# Ver_5_MD_Nch.net
KiCad netlist of a schematic drawn in EAGLE
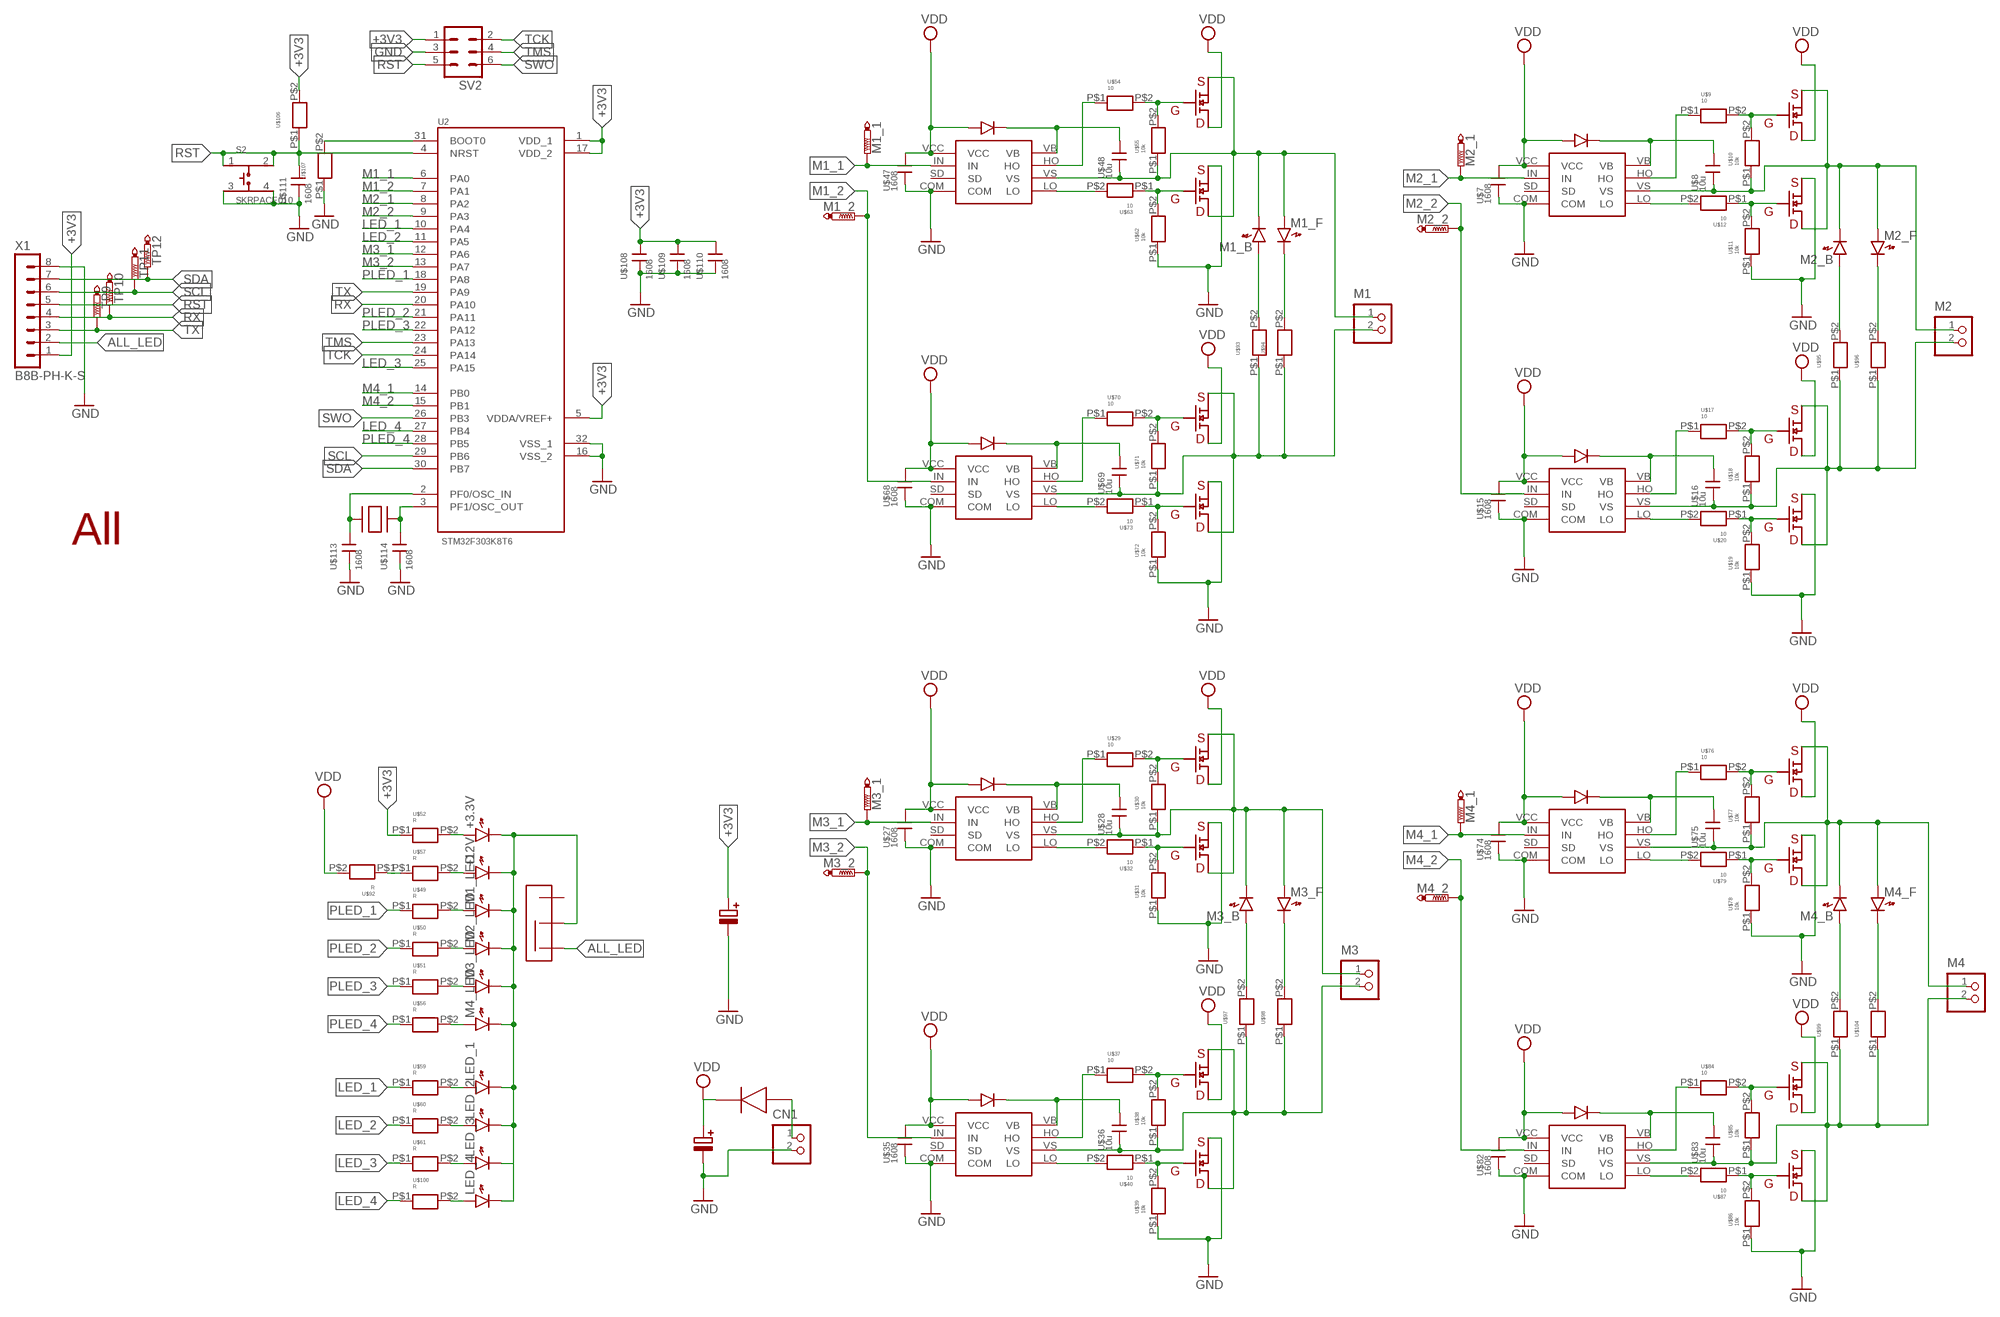
[diagram p0: schematic, sheet 1]

(export (version "E")
  (design (tool "Eeschema 10.0.6"))
  (components
    (comp (ref "+3.3V")
      (value "LED1608")
      (footprint "eagle-import:LED1608")
      (libsource (lib "eagle-import") (part "LED1608"))
    )
    (comp (ref "+12V")
      (value "LED1608")
      (footprint "eagle-import:LED1608")
      (libsource (lib "eagle-import") (part "LED1608"))
    )
    (comp (ref "CN1")
      (value "B2B-XH-A")
      (footprint "eagle-import:B2B-XH-A")
      (libsource (lib "eagle-import") (part "B2B-XH-A"))
    )
    (comp (ref "LED_1")
      (value "LED1608")
      (footprint "eagle-import:LED1608")
      (libsource (lib "eagle-import") (part "LED1608"))
    )
    (comp (ref "LED_2")
      (value "LED1608")
      (footprint "eagle-import:LED1608")
      (libsource (lib "eagle-import") (part "LED1608"))
    )
    (comp (ref "LED_3")
      (value "LED1608")
      (footprint "eagle-import:LED1608")
      (libsource (lib "eagle-import") (part "LED1608"))
    )
    (comp (ref "LED_4")
      (value "LED1608")
      (footprint "eagle-import:LED1608")
      (libsource (lib "eagle-import") (part "LED1608"))
    )
    (comp (ref "M1")
      (value "S2B-XH-A")
      (footprint "eagle-import:S2B-XH-A")
      (libsource (lib "eagle-import") (part "S2B-XH-A"))
    )
    (comp (ref "M1_1")
      (value "PTR1B1,27")
      (footprint "eagle-import:B1,27")
      (libsource (lib "eagle-import") (part "PTR1B1,27"))
    )
    (comp (ref "M1_2")
      (value "PTR1B1,27")
      (footprint "eagle-import:B1,27")
      (libsource (lib "eagle-import") (part "PTR1B1,27"))
    )
    (comp (ref "M1_B")
      (value "LED1608")
      (footprint "eagle-import:LED1608")
      (libsource (lib "eagle-import") (part "LED1608"))
    )
    (comp (ref "M1_F")
      (value "LED1608")
      (footprint "eagle-import:LED1608")
      (libsource (lib "eagle-import") (part "LED1608"))
    )
    (comp (ref "M1_LED")
      (value "LED1608")
      (footprint "eagle-import:LED1608")
      (libsource (lib "eagle-import") (part "LED1608"))
    )
    (comp (ref "M2")
      (value "S2B-XH-A")
      (footprint "eagle-import:S2B-XH-A")
      (libsource (lib "eagle-import") (part "S2B-XH-A"))
    )
    (comp (ref "M2_1")
      (value "PTR1B1,27")
      (footprint "eagle-import:B1,27")
      (libsource (lib "eagle-import") (part "PTR1B1,27"))
    )
    (comp (ref "M2_2")
      (value "PTR1B1,27")
      (footprint "eagle-import:B1,27")
      (libsource (lib "eagle-import") (part "PTR1B1,27"))
    )
    (comp (ref "M2_B")
      (value "LED1608")
      (footprint "eagle-import:LED1608")
      (libsource (lib "eagle-import") (part "LED1608"))
    )
    (comp (ref "M2_F")
      (value "LED1608")
      (footprint "eagle-import:LED1608")
      (libsource (lib "eagle-import") (part "LED1608"))
    )
    (comp (ref "M2_LED")
      (value "LED1608")
      (footprint "eagle-import:LED1608")
      (libsource (lib "eagle-import") (part "LED1608"))
    )
    (comp (ref "M3")
      (value "S2B-XH-A")
      (footprint "eagle-import:S2B-XH-A")
      (libsource (lib "eagle-import") (part "S2B-XH-A"))
    )
    (comp (ref "M3_1")
      (value "PTR1B1,27")
      (footprint "eagle-import:B1,27")
      (libsource (lib "eagle-import") (part "PTR1B1,27"))
    )
    (comp (ref "M3_2")
      (value "PTR1B1,27")
      (footprint "eagle-import:B1,27")
      (libsource (lib "eagle-import") (part "PTR1B1,27"))
    )
    (comp (ref "M3_B")
      (value "LED1608")
      (footprint "eagle-import:LED1608")
      (libsource (lib "eagle-import") (part "LED1608"))
    )
    (comp (ref "M3_F")
      (value "LED1608")
      (footprint "eagle-import:LED1608")
      (libsource (lib "eagle-import") (part "LED1608"))
    )
    (comp (ref "M3_LED")
      (value "LED1608")
      (footprint "eagle-import:LED1608")
      (libsource (lib "eagle-import") (part "LED1608"))
    )
    (comp (ref "M4")
      (value "S2B-XH-A")
      (footprint "eagle-import:S2B-XH-A")
      (libsource (lib "eagle-import") (part "S2B-XH-A"))
    )
    (comp (ref "M4_1")
      (value "PTR1B1,27")
      (footprint "eagle-import:B1,27")
      (libsource (lib "eagle-import") (part "PTR1B1,27"))
    )
    (comp (ref "M4_2")
      (value "PTR1B1,27")
      (footprint "eagle-import:B1,27")
      (libsource (lib "eagle-import") (part "PTR1B1,27"))
    )
    (comp (ref "M4_B")
      (value "LED1608")
      (footprint "eagle-import:LED1608")
      (libsource (lib "eagle-import") (part "LED1608"))
    )
    (comp (ref "M4_F")
      (value "LED1608")
      (footprint "eagle-import:LED1608")
      (libsource (lib "eagle-import") (part "LED1608"))
    )
    (comp (ref "M4_LED")
      (value "LED1608")
      (footprint "eagle-import:LED1608")
      (libsource (lib "eagle-import") (part "LED1608"))
    )
    (comp (ref "S2")
      (value "SKRPACE010")
      (footprint "eagle-import:SW_SKRPACE010")
      (fields (field (name "MF") "ALPS"))
      (libsource (lib "eagle-import") (part "SKRPACE010"))
    )
    (comp (ref "SV2")
      (value "ML6")
      (footprint "eagle-import:ML6")
      (libsource (lib "eagle-import") (part "ML6"))
    )
    (comp (ref "TP9")
      (value "PTR1B1,27")
      (footprint "eagle-import:B1,27")
      (libsource (lib "eagle-import") (part "PTR1B1,27"))
    )
    (comp (ref "TP10")
      (value "PTR1B1,27")
      (footprint "eagle-import:B1,27")
      (libsource (lib "eagle-import") (part "PTR1B1,27"))
    )
    (comp (ref "TP11")
      (value "PTR1B1,27")
      (footprint "eagle-import:B1,27")
      (libsource (lib "eagle-import") (part "PTR1B1,27"))
    )
    (comp (ref "TP12")
      (value "PTR1B1,27")
      (footprint "eagle-import:B1,27")
      (libsource (lib "eagle-import") (part "PTR1B1,27"))
    )
    (comp (ref "U$1")
      (value "SSM6K8")
      (footprint "eagle-import:SSM6K8")
      (libsource (lib "eagle-import") (part "SSM6K8"))
    )
    (comp (ref "U$2")
      (value "SSM6K8")
      (footprint "eagle-import:SSM6K8")
      (libsource (lib "eagle-import") (part "SSM6K8"))
    )
    (comp (ref "U$3")
      (value "SSM6K8")
      (footprint "eagle-import:SSM6K8")
      (libsource (lib "eagle-import") (part "SSM6K8"))
    )
    (comp (ref "U$4")
      (value "SSM6K8")
      (footprint "eagle-import:SSM6K8")
      (libsource (lib "eagle-import") (part "SSM6K8"))
    )
    (comp (ref "U$5")
      (value "IR2302")
      (footprint "eagle-import:IR2302")
      (libsource (lib "eagle-import") (part "IR2302"))
    )
    (comp (ref "U$6")
      (value "1N4148")
      (footprint "eagle-import:1N4148")
      (libsource (lib "eagle-import") (part "1N4148"))
    )
    (comp (ref "U$7")
      (value "1608")
      (footprint "eagle-import:CON")
      (libsource (lib "eagle-import") (part "1608"))
    )
    (comp (ref "U$8")
      (value "10u")
      (footprint "eagle-import:CON")
      (libsource (lib "eagle-import") (part "1608"))
    )
    (comp (ref "U$9")
      (value "10")
      (footprint "eagle-import:1608")
      (libsource (lib "eagle-import") (part "R"))
    )
    (comp (ref "U$10")
      (value "10k")
      (footprint "eagle-import:1608")
      (libsource (lib "eagle-import") (part "R"))
    )
    (comp (ref "U$11")
      (value "10k")
      (footprint "eagle-import:1608")
      (libsource (lib "eagle-import") (part "R"))
    )
    (comp (ref "U$12")
      (value "10")
      (footprint "eagle-import:1608")
      (libsource (lib "eagle-import") (part "R"))
    )
    (comp (ref "U$13")
      (value "IR2302")
      (footprint "eagle-import:IR2302")
      (libsource (lib "eagle-import") (part "IR2302"))
    )
    (comp (ref "U$14")
      (value "1N4148")
      (footprint "eagle-import:1N4148")
      (libsource (lib "eagle-import") (part "1N4148"))
    )
    (comp (ref "U$15")
      (value "1608")
      (footprint "eagle-import:CON")
      (libsource (lib "eagle-import") (part "1608"))
    )
    (comp (ref "U$16")
      (value "10u")
      (footprint "eagle-import:CON")
      (libsource (lib "eagle-import") (part "1608"))
    )
    (comp (ref "U$17")
      (value "10")
      (footprint "eagle-import:1608")
      (libsource (lib "eagle-import") (part "R"))
    )
    (comp (ref "U$18")
      (value "10k")
      (footprint "eagle-import:1608")
      (libsource (lib "eagle-import") (part "R"))
    )
    (comp (ref "U$19")
      (value "10k")
      (footprint "eagle-import:1608")
      (libsource (lib "eagle-import") (part "R"))
    )
    (comp (ref "U$20")
      (value "10")
      (footprint "eagle-import:1608")
      (libsource (lib "eagle-import") (part "R"))
    )
    (comp (ref "U$21")
      (value "SSM6K8")
      (footprint "eagle-import:SSM6K8")
      (libsource (lib "eagle-import") (part "SSM6K8"))
    )
    (comp (ref "U$22")
      (value "SSM6K8")
      (footprint "eagle-import:SSM6K8")
      (libsource (lib "eagle-import") (part "SSM6K8"))
    )
    (comp (ref "U$23")
      (value "SSM6K8")
      (footprint "eagle-import:SSM6K8")
      (libsource (lib "eagle-import") (part "SSM6K8"))
    )
    (comp (ref "U$24")
      (value "SSM6K8")
      (footprint "eagle-import:SSM6K8")
      (libsource (lib "eagle-import") (part "SSM6K8"))
    )
    (comp (ref "U$25")
      (value "IR2302")
      (footprint "eagle-import:IR2302")
      (libsource (lib "eagle-import") (part "IR2302"))
    )
    (comp (ref "U$26")
      (value "1N4148")
      (footprint "eagle-import:1N4148")
      (libsource (lib "eagle-import") (part "1N4148"))
    )
    (comp (ref "U$27")
      (value "1608")
      (footprint "eagle-import:CON")
      (libsource (lib "eagle-import") (part "1608"))
    )
    (comp (ref "U$28")
      (value "10u")
      (footprint "eagle-import:CON")
      (libsource (lib "eagle-import") (part "1608"))
    )
    (comp (ref "U$29")
      (value "10")
      (footprint "eagle-import:1608")
      (libsource (lib "eagle-import") (part "R"))
    )
    (comp (ref "U$30")
      (value "10k")
      (footprint "eagle-import:1608")
      (libsource (lib "eagle-import") (part "R"))
    )
    (comp (ref "U$31")
      (value "10k")
      (footprint "eagle-import:1608")
      (libsource (lib "eagle-import") (part "R"))
    )
    (comp (ref "U$32")
      (value "10")
      (footprint "eagle-import:1608")
      (libsource (lib "eagle-import") (part "R"))
    )
    (comp (ref "U$33")
      (value "IR2302")
      (footprint "eagle-import:IR2302")
      (libsource (lib "eagle-import") (part "IR2302"))
    )
    (comp (ref "U$34")
      (value "1N4148")
      (footprint "eagle-import:1N4148")
      (libsource (lib "eagle-import") (part "1N4148"))
    )
    (comp (ref "U$35")
      (value "1608")
      (footprint "eagle-import:CON")
      (libsource (lib "eagle-import") (part "1608"))
    )
    (comp (ref "U$36")
      (value "10u")
      (footprint "eagle-import:CON")
      (libsource (lib "eagle-import") (part "1608"))
    )
    (comp (ref "U$37")
      (value "10")
      (footprint "eagle-import:1608")
      (libsource (lib "eagle-import") (part "R"))
    )
    (comp (ref "U$38")
      (value "10k")
      (footprint "eagle-import:1608")
      (libsource (lib "eagle-import") (part "R"))
    )
    (comp (ref "U$39")
      (value "10k")
      (footprint "eagle-import:1608")
      (libsource (lib "eagle-import") (part "R"))
    )
    (comp (ref "U$40")
      (value "10")
      (footprint "eagle-import:1608")
      (libsource (lib "eagle-import") (part "R"))
    )
    (comp (ref "U$41")
      (value "SSM6K8")
      (footprint "eagle-import:SSM6K8")
      (libsource (lib "eagle-import") (part "SSM6K8"))
    )
    (comp (ref "U$42")
      (value "SSM6K8")
      (footprint "eagle-import:SSM6K8")
      (libsource (lib "eagle-import") (part "SSM6K8"))
    )
    (comp (ref "U$43")
      (value "SSM6K8")
      (footprint "eagle-import:SSM6K8")
      (libsource (lib "eagle-import") (part "SSM6K8"))
    )
    (comp (ref "U$44")
      (value "SSM6K8")
      (footprint "eagle-import:SSM6K8")
      (libsource (lib "eagle-import") (part "SSM6K8"))
    )
    (comp (ref "U$45")
      (value "IR2302")
      (footprint "eagle-import:IR2302")
      (libsource (lib "eagle-import") (part "IR2302"))
    )
    (comp (ref "U$46")
      (value "1N4148")
      (footprint "eagle-import:1N4148")
      (libsource (lib "eagle-import") (part "1N4148"))
    )
    (comp (ref "U$47")
      (value "1608")
      (footprint "eagle-import:CON")
      (libsource (lib "eagle-import") (part "1608"))
    )
    (comp (ref "U$48")
      (value "10u")
      (footprint "eagle-import:CON")
      (libsource (lib "eagle-import") (part "1608"))
    )
    (comp (ref "U$49")
      (value "R")
      (footprint "eagle-import:1608")
      (libsource (lib "eagle-import") (part "R"))
    )
    (comp (ref "U$50")
      (value "R")
      (footprint "eagle-import:1608")
      (libsource (lib "eagle-import") (part "R"))
    )
    (comp (ref "U$51")
      (value "R")
      (footprint "eagle-import:1608")
      (libsource (lib "eagle-import") (part "R"))
    )
    (comp (ref "U$52")
      (value "R")
      (footprint "eagle-import:1608")
      (libsource (lib "eagle-import") (part "R"))
    )
    (comp (ref "U$53")
      (value "SSW")
      (footprint "eagle-import:SSW")
      (libsource (lib "eagle-import") (part "SSW"))
    )
    (comp (ref "U$54")
      (value "10")
      (footprint "eagle-import:1608")
      (libsource (lib "eagle-import") (part "R"))
    )
    (comp (ref "U$55")
      (value "10k")
      (footprint "eagle-import:1608")
      (libsource (lib "eagle-import") (part "R"))
    )
    (comp (ref "U$56")
      (value "R")
      (footprint "eagle-import:1608")
      (libsource (lib "eagle-import") (part "R"))
    )
    (comp (ref "U$57")
      (value "R")
      (footprint "eagle-import:1608")
      (libsource (lib "eagle-import") (part "R"))
    )
    (comp (ref "U$58")
      (value "25V100")
      (footprint "eagle-import:25V100")
      (libsource (lib "eagle-import") (part "25V100"))
    )
    (comp (ref "U$59")
      (value "R")
      (footprint "eagle-import:1608")
      (libsource (lib "eagle-import") (part "R"))
    )
    (comp (ref "U$60")
      (value "R")
      (footprint "eagle-import:1608")
      (libsource (lib "eagle-import") (part "R"))
    )
    (comp (ref "U$61")
      (value "R")
      (footprint "eagle-import:1608")
      (libsource (lib "eagle-import") (part "R"))
    )
    (comp (ref "U$62")
      (value "10k")
      (footprint "eagle-import:1608")
      (libsource (lib "eagle-import") (part "R"))
    )
    (comp (ref "U$63")
      (value "10")
      (footprint "eagle-import:1608")
      (libsource (lib "eagle-import") (part "R"))
    )
    (comp (ref "U$64")
      (value "IR2302")
      (footprint "eagle-import:IR2302")
      (libsource (lib "eagle-import") (part "IR2302"))
    )
    (comp (ref "U$65")
      (value "1N4148")
      (footprint "eagle-import:1N4148")
      (libsource (lib "eagle-import") (part "1N4148"))
    )
    (comp (ref "U$66")
      (value "IR2302")
      (footprint "eagle-import:IR2302")
      (libsource (lib "eagle-import") (part "IR2302"))
    )
    (comp (ref "U$67")
      (value "1N4148")
      (footprint "eagle-import:1N4148")
      (libsource (lib "eagle-import") (part "1N4148"))
    )
    (comp (ref "U$68")
      (value "1608")
      (footprint "eagle-import:CON")
      (libsource (lib "eagle-import") (part "1608"))
    )
    (comp (ref "U$69")
      (value "10u")
      (footprint "eagle-import:CON")
      (libsource (lib "eagle-import") (part "1608"))
    )
    (comp (ref "U$70")
      (value "10")
      (footprint "eagle-import:1608")
      (libsource (lib "eagle-import") (part "R"))
    )
    (comp (ref "U$71")
      (value "10k")
      (footprint "eagle-import:1608")
      (libsource (lib "eagle-import") (part "R"))
    )
    (comp (ref "U$72")
      (value "10k")
      (footprint "eagle-import:1608")
      (libsource (lib "eagle-import") (part "R"))
    )
    (comp (ref "U$73")
      (value "10")
      (footprint "eagle-import:1608")
      (libsource (lib "eagle-import") (part "R"))
    )
    (comp (ref "U$74")
      (value "1608")
      (footprint "eagle-import:CON")
      (libsource (lib "eagle-import") (part "1608"))
    )
    (comp (ref "U$75")
      (value "10u")
      (footprint "eagle-import:CON")
      (libsource (lib "eagle-import") (part "1608"))
    )
    (comp (ref "U$76")
      (value "10")
      (footprint "eagle-import:1608")
      (libsource (lib "eagle-import") (part "R"))
    )
    (comp (ref "U$77")
      (value "10k")
      (footprint "eagle-import:1608")
      (libsource (lib "eagle-import") (part "R"))
    )
    (comp (ref "U$78")
      (value "10k")
      (footprint "eagle-import:1608")
      (libsource (lib "eagle-import") (part "R"))
    )
    (comp (ref "U$79")
      (value "10")
      (footprint "eagle-import:1608")
      (libsource (lib "eagle-import") (part "R"))
    )
    (comp (ref "U$80")
      (value "IR2302")
      (footprint "eagle-import:IR2302")
      (libsource (lib "eagle-import") (part "IR2302"))
    )
    (comp (ref "U$81")
      (value "1N4148")
      (footprint "eagle-import:1N4148")
      (libsource (lib "eagle-import") (part "1N4148"))
    )
    (comp (ref "U$82")
      (value "1608")
      (footprint "eagle-import:CON")
      (libsource (lib "eagle-import") (part "1608"))
    )
    (comp (ref "U$83")
      (value "10u")
      (footprint "eagle-import:CON")
      (libsource (lib "eagle-import") (part "1608"))
    )
    (comp (ref "U$84")
      (value "10")
      (footprint "eagle-import:1608")
      (libsource (lib "eagle-import") (part "R"))
    )
    (comp (ref "U$85")
      (value "10k")
      (footprint "eagle-import:1608")
      (libsource (lib "eagle-import") (part "R"))
    )
    (comp (ref "U$86")
      (value "10k")
      (footprint "eagle-import:1608")
      (libsource (lib "eagle-import") (part "R"))
    )
    (comp (ref "U$87")
      (value "10")
      (footprint "eagle-import:1608")
      (libsource (lib "eagle-import") (part "R"))
    )
    (comp (ref "U$88")
      (value "SSM6K8")
      (footprint "eagle-import:SSM6K8")
      (libsource (lib "eagle-import") (part "SSM6K8"))
    )
    (comp (ref "U$89")
      (value "SSM6K8")
      (footprint "eagle-import:SSM6K8")
      (libsource (lib "eagle-import") (part "SSM6K8"))
    )
    (comp (ref "U$90")
      (value "SSM6K8")
      (footprint "eagle-import:SSM6K8")
      (libsource (lib "eagle-import") (part "SSM6K8"))
    )
    (comp (ref "U$91")
      (value "SSM6K8")
      (footprint "eagle-import:SSM6K8")
      (libsource (lib "eagle-import") (part "SSM6K8"))
    )
    (comp (ref "U$92")
      (value "R")
      (footprint "eagle-import:1608")
      (libsource (lib "eagle-import") (part "R"))
    )
    (comp (ref "U$93")
      (value "R")
      (footprint "eagle-import:1608")
      (libsource (lib "eagle-import") (part "R"))
    )
    (comp (ref "U$94")
      (value "R")
      (footprint "eagle-import:1608")
      (libsource (lib "eagle-import") (part "R"))
    )
    (comp (ref "U$95")
      (value "R")
      (footprint "eagle-import:1608")
      (libsource (lib "eagle-import") (part "R"))
    )
    (comp (ref "U$96")
      (value "R")
      (footprint "eagle-import:1608")
      (libsource (lib "eagle-import") (part "R"))
    )
    (comp (ref "U$97")
      (value "R")
      (footprint "eagle-import:1608")
      (libsource (lib "eagle-import") (part "R"))
    )
    (comp (ref "U$98")
      (value "R")
      (footprint "eagle-import:1608")
      (libsource (lib "eagle-import") (part "R"))
    )
    (comp (ref "U$99")
      (value "R")
      (footprint "eagle-import:1608")
      (libsource (lib "eagle-import") (part "R"))
    )
    (comp (ref "U$100")
      (value "R")
      (footprint "eagle-import:1608")
      (libsource (lib "eagle-import") (part "R"))
    )
    (comp (ref "U$101")
      (value "25V100")
      (footprint "eagle-import:25V100")
      (libsource (lib "eagle-import") (part "25V100"))
    )
    (comp (ref "U$102")
      (value "40V5A")
      (footprint "eagle-import:40V5A")
      (libsource (lib "eagle-import") (part "40V5A"))
    )
    (comp (ref "U$103")
      (value "ALL")
      (footprint "eagle-import:ALL")
      (libsource (lib "eagle-import") (part "ALL"))
    )
    (comp (ref "U$104")
      (value "R")
      (footprint "eagle-import:1608")
      (libsource (lib "eagle-import") (part "R"))
    )
    (comp (ref "U$106")
      (value "R")
      (footprint "eagle-import:1608")
      (libsource (lib "eagle-import") (part "R"))
    )
    (comp (ref "U$107")
      (value "R")
      (footprint "eagle-import:1608")
      (libsource (lib "eagle-import") (part "R"))
    )
    (comp (ref "U$108")
      (value "1608")
      (footprint "eagle-import:CON")
      (libsource (lib "eagle-import") (part "1608"))
    )
    (comp (ref "U$109")
      (value "1608")
      (footprint "eagle-import:CON")
      (libsource (lib "eagle-import") (part "1608"))
    )
    (comp (ref "U$110")
      (value "1608")
      (footprint "eagle-import:CON")
      (libsource (lib "eagle-import") (part "1608"))
    )
    (comp (ref "U$111")
      (value "1608")
      (footprint "eagle-import:CON")
      (libsource (lib "eagle-import") (part "1608"))
    )
    (comp (ref "U$112")
      (value "SUISYOU")
      (footprint "eagle-import:水晶")
      (libsource (lib "eagle-import") (part "SUISYOU"))
    )
    (comp (ref "U$113")
      (value "1608")
      (footprint "eagle-import:CON")
      (libsource (lib "eagle-import") (part "1608"))
    )
    (comp (ref "U$114")
      (value "1608")
      (footprint "eagle-import:CON")
      (libsource (lib "eagle-import") (part "1608"))
    )
    (comp (ref "U2")
      (value "STM32F303K8T6")
      (footprint "eagle-import:QFP80P900X900X160-32N")
      (fields (field (name "MF") "STMicroelectronics"))
      (libsource (lib "eagle-import") (part "STM32F303K8T6"))
    )
    (comp (ref "X1")
      (value "B8B-PH-K-S")
      (footprint "eagle-import:B8B-PH-K-S")
      (libsource (lib "eagle-import") (part "B8B-PH-K-S"))
    )
  )
  (nets
    (net (code "1") (name "+3V3") (class "Default")
      (node (ref "SV2") (pin "1") (pinfunction "1_1") (pintype "passive"))
      (node (ref "U$106") (pin "P$2") (pinfunction "P$2_P$2") (pintype "bidirectional"))
      (node (ref "U$108") (pin "P$1") (pinfunction "1_P$1") (pintype "bidirectional"))
      (node (ref "U$109") (pin "P$1") (pinfunction "1_P$1") (pintype "bidirectional"))
      (node (ref "U$110") (pin "P$1") (pinfunction "1_P$1") (pintype "bidirectional"))
      (node (ref "U$52") (pin "P$1") (pinfunction "P$1_P$1") (pintype "bidirectional"))
      (node (ref "U$58") (pin "P$1") (pinfunction "P$1_P$1") (pintype "bidirectional"))
      (node (ref "U2") (pin "1") (pinfunction "VDD_1_1") (pintype "power_in"))
      (node (ref "U2") (pin "17") (pinfunction "VDD_2_17") (pintype "power_in"))
      (node (ref "U2") (pin "5") (pinfunction "VDDA/VREF+_5") (pintype "power_in"))
      (node (ref "X1") (pin "1") (pinfunction "1_1") (pintype "passive"))
    )
    (net (code "2") (name "ALL_LED") (class "Default")
      (node (ref "U$53") (pin "P$1") (pinfunction "P$1_P$1") (pintype "bidirectional"))
      (node (ref "X1") (pin "2") (pinfunction "2_2") (pintype "passive"))
    )
    (net (code "3") (name "GND") (class "Default")
      (node (ref "CN1") (pin "2") (pinfunction "2_2") (pintype "passive"))
      (node (ref "S2") (pin "3") (pinfunction "3_3") (pintype "bidirectional"))
      (node (ref "S2") (pin "4") (pinfunction "4_4") (pintype "bidirectional"))
      (node (ref "SV2") (pin "3") (pinfunction "3_3") (pintype "passive"))
      (node (ref "U$101") (pin "P$2") (pinfunction "P$2_P$2") (pintype "bidirectional"))
      (node (ref "U$107") (pin "P$1") (pinfunction "P$1_P$1") (pintype "bidirectional"))
      (node (ref "U$108") (pin "P$2") (pinfunction "2_P$2") (pintype "bidirectional"))
      (node (ref "U$109") (pin "P$2") (pinfunction "2_P$2") (pintype "bidirectional"))
      (node (ref "U$11") (pin "P$1") (pinfunction "P$1_P$1") (pintype "bidirectional"))
      (node (ref "U$110") (pin "P$2") (pinfunction "2_P$2") (pintype "bidirectional"))
      (node (ref "U$111") (pin "P$2") (pinfunction "2_P$2") (pintype "bidirectional"))
      (node (ref "U$113") (pin "P$2") (pinfunction "2_P$2") (pintype "bidirectional"))
      (node (ref "U$114") (pin "P$2") (pinfunction "2_P$2") (pintype "bidirectional"))
      (node (ref "U$13") (pin "COM") (pinfunction "COM_COM") (pintype "bidirectional"))
      (node (ref "U$15") (pin "P$2") (pinfunction "2_P$2") (pintype "bidirectional"))
      (node (ref "U$19") (pin "P$1") (pinfunction "P$1_P$1") (pintype "bidirectional"))
      (node (ref "U$2") (pin "S") (pinfunction "S_S") (pintype "bidirectional"))
      (node (ref "U$22") (pin "S") (pinfunction "S_S") (pintype "bidirectional"))
      (node (ref "U$24") (pin "S") (pinfunction "S_S") (pintype "bidirectional"))
      (node (ref "U$25") (pin "COM") (pinfunction "COM_COM") (pintype "bidirectional"))
      (node (ref "U$27") (pin "P$2") (pinfunction "2_P$2") (pintype "bidirectional"))
      (node (ref "U$31") (pin "P$1") (pinfunction "P$1_P$1") (pintype "bidirectional"))
      (node (ref "U$33") (pin "COM") (pinfunction "COM_COM") (pintype "bidirectional"))
      (node (ref "U$35") (pin "P$2") (pinfunction "2_P$2") (pintype "bidirectional"))
      (node (ref "U$39") (pin "P$1") (pinfunction "P$1_P$1") (pintype "bidirectional"))
      (node (ref "U$4") (pin "S") (pinfunction "S_S") (pintype "bidirectional"))
      (node (ref "U$42") (pin "S") (pinfunction "S_S") (pintype "bidirectional"))
      (node (ref "U$44") (pin "S") (pinfunction "S_S") (pintype "bidirectional"))
      (node (ref "U$45") (pin "COM") (pinfunction "COM_COM") (pintype "bidirectional"))
      (node (ref "U$47") (pin "P$2") (pinfunction "2_P$2") (pintype "bidirectional"))
      (node (ref "U$5") (pin "COM") (pinfunction "COM_COM") (pintype "bidirectional"))
      (node (ref "U$58") (pin "P$2") (pinfunction "P$2_P$2") (pintype "bidirectional"))
      (node (ref "U$62") (pin "P$1") (pinfunction "P$1_P$1") (pintype "bidirectional"))
      (node (ref "U$64") (pin "COM") (pinfunction "COM_COM") (pintype "bidirectional"))
      (node (ref "U$66") (pin "COM") (pinfunction "COM_COM") (pintype "bidirectional"))
      (node (ref "U$68") (pin "P$2") (pinfunction "2_P$2") (pintype "bidirectional"))
      (node (ref "U$7") (pin "P$2") (pinfunction "2_P$2") (pintype "bidirectional"))
      (node (ref "U$72") (pin "P$1") (pinfunction "P$1_P$1") (pintype "bidirectional"))
      (node (ref "U$74") (pin "P$2") (pinfunction "2_P$2") (pintype "bidirectional"))
      (node (ref "U$78") (pin "P$1") (pinfunction "P$1_P$1") (pintype "bidirectional"))
      (node (ref "U$80") (pin "COM") (pinfunction "COM_COM") (pintype "bidirectional"))
      (node (ref "U$82") (pin "P$2") (pinfunction "2_P$2") (pintype "bidirectional"))
      (node (ref "U$86") (pin "P$1") (pinfunction "P$1_P$1") (pintype "bidirectional"))
      (node (ref "U$89") (pin "S") (pinfunction "S_S") (pintype "bidirectional"))
      (node (ref "U$91") (pin "S") (pinfunction "S_S") (pintype "bidirectional"))
      (node (ref "U2") (pin "16") (pinfunction "VSS_2_16") (pintype "power_in"))
      (node (ref "U2") (pin "32") (pinfunction "VSS_1_32") (pintype "power_in"))
      (node (ref "X1") (pin "8") (pinfunction "8_8") (pintype "passive"))
    )
    (net (code "4") (name "LED_1") (class "Default")
      (node (ref "U$59") (pin "P$1") (pinfunction "P$1_P$1") (pintype "bidirectional"))
      (node (ref "U2") (pin "10") (pinfunction "PA4_10") (pintype "bidirectional"))
    )
    (net (code "5") (name "LED_2") (class "Default")
      (node (ref "U$60") (pin "P$1") (pinfunction "P$1_P$1") (pintype "bidirectional"))
      (node (ref "U2") (pin "11") (pinfunction "PA5_11") (pintype "bidirectional"))
    )
    (net (code "6") (name "LED_3") (class "Default")
      (node (ref "U$61") (pin "P$1") (pinfunction "P$1_P$1") (pintype "bidirectional"))
      (node (ref "U2") (pin "25") (pinfunction "PA15_25") (pintype "bidirectional"))
    )
    (net (code "7") (name "LED_4") (class "Default")
      (node (ref "U$100") (pin "P$1") (pinfunction "P$1_P$1") (pintype "bidirectional"))
      (node (ref "U2") (pin "27") (pinfunction "PB4_27") (pintype "bidirectional"))
    )
    (net (code "8") (name "M1_1") (class "Default")
      (node (ref "M1_1") (pin "TP") (pinfunction "TP_TP") (pintype "input"))
      (node (ref "U$45") (pin "IN") (pinfunction "IN_IN") (pintype "bidirectional"))
      (node (ref "U2") (pin "6") (pinfunction "PA0_6") (pintype "bidirectional"))
    )
    (net (code "9") (name "M1_2") (class "Default")
      (node (ref "M1_2") (pin "TP") (pinfunction "TP_TP") (pintype "input"))
      (node (ref "U$66") (pin "IN") (pinfunction "IN_IN") (pintype "bidirectional"))
      (node (ref "U2") (pin "7") (pinfunction "PA1_7") (pintype "bidirectional"))
    )
    (net (code "10") (name "M2_1") (class "Default")
      (node (ref "M2_1") (pin "TP") (pinfunction "TP_TP") (pintype "input"))
      (node (ref "U$5") (pin "IN") (pinfunction "IN_IN") (pintype "bidirectional"))
      (node (ref "U2") (pin "8") (pinfunction "PA2_8") (pintype "bidirectional"))
    )
    (net (code "11") (name "M2_2") (class "Default")
      (node (ref "M2_2") (pin "TP") (pinfunction "TP_TP") (pintype "input"))
      (node (ref "U$13") (pin "IN") (pinfunction "IN_IN") (pintype "bidirectional"))
      (node (ref "U2") (pin "9") (pinfunction "PA3_9") (pintype "bidirectional"))
    )
    (net (code "12") (name "M3_1") (class "Default")
      (node (ref "M3_1") (pin "TP") (pinfunction "TP_TP") (pintype "input"))
      (node (ref "U$25") (pin "IN") (pinfunction "IN_IN") (pintype "bidirectional"))
      (node (ref "U2") (pin "12") (pinfunction "PA6_12") (pintype "bidirectional"))
    )
    (net (code "13") (name "M3_2") (class "Default")
      (node (ref "M3_2") (pin "TP") (pinfunction "TP_TP") (pintype "input"))
      (node (ref "U$33") (pin "IN") (pinfunction "IN_IN") (pintype "bidirectional"))
      (node (ref "U2") (pin "13") (pinfunction "PA7_13") (pintype "bidirectional"))
    )
    (net (code "14") (name "M4_1") (class "Default")
      (node (ref "M4_1") (pin "TP") (pinfunction "TP_TP") (pintype "input"))
      (node (ref "U$64") (pin "IN") (pinfunction "IN_IN") (pintype "bidirectional"))
      (node (ref "U2") (pin "14") (pinfunction "PB0_14") (pintype "bidirectional"))
    )
    (net (code "15") (name "M4_2") (class "Default")
      (node (ref "M4_2") (pin "TP") (pinfunction "TP_TP") (pintype "input"))
      (node (ref "U$80") (pin "IN") (pinfunction "IN_IN") (pintype "bidirectional"))
      (node (ref "U2") (pin "15") (pinfunction "PB1_15") (pintype "bidirectional"))
    )
    (net (code "16") (name "Net-(+3.3V-PadA)") (class "Default")
      (node (ref "+3.3V") (pin "A") (pinfunction "A_A") (pintype "passive"))
      (node (ref "U$52") (pin "P$2") (pinfunction "P$2_P$2") (pintype "bidirectional"))
    )
    (net (code "17") (name "Net-(+12V-PadA)") (class "Default")
      (node (ref "+12V") (pin "A") (pinfunction "A_A") (pintype "passive"))
      (node (ref "U$57") (pin "P$2") (pinfunction "P$2_P$2") (pintype "bidirectional"))
    )
    (net (code "18") (name "Net-(CN1-Pad1)") (class "Default")
      (node (ref "CN1") (pin "1") (pinfunction "1_1") (pintype "passive"))
      (node (ref "U$102") (pin "P$1") (pinfunction "P$1_P$1") (pintype "bidirectional"))
    )
    (net (code "19") (name "Net-(LED_1-PadA)") (class "Default")
      (node (ref "LED_1") (pin "A") (pinfunction "A_A") (pintype "passive"))
      (node (ref "U$59") (pin "P$2") (pinfunction "P$2_P$2") (pintype "bidirectional"))
    )
    (net (code "20") (name "Net-(LED_2-PadA)") (class "Default")
      (node (ref "LED_2") (pin "A") (pinfunction "A_A") (pintype "passive"))
      (node (ref "U$60") (pin "P$2") (pinfunction "P$2_P$2") (pintype "bidirectional"))
    )
    (net (code "21") (name "Net-(LED_3-PadA)") (class "Default")
      (node (ref "LED_3") (pin "A") (pinfunction "A_A") (pintype "passive"))
      (node (ref "U$61") (pin "P$2") (pinfunction "P$2_P$2") (pintype "bidirectional"))
    )
    (net (code "22") (name "Net-(LED_4-PadA)") (class "Default")
      (node (ref "LED_4") (pin "A") (pinfunction "A_A") (pintype "passive"))
      (node (ref "U$100") (pin "P$2") (pinfunction "P$2_P$2") (pintype "bidirectional"))
    )
    (net (code "23") (name "Net-(M1_B-PadA)") (class "Default")
      (node (ref "M1_B") (pin "A") (pinfunction "A_A") (pintype "passive"))
      (node (ref "U$93") (pin "P$2") (pinfunction "P$2_P$2") (pintype "bidirectional"))
    )
    (net (code "24") (name "Net-(M1_F-PadK)") (class "Default")
      (node (ref "M1_F") (pin "K") (pinfunction "K_K") (pintype "passive"))
      (node (ref "U$94") (pin "P$2") (pinfunction "P$2_P$2") (pintype "bidirectional"))
    )
    (net (code "25") (name "Net-(M1_LED-PadA)") (class "Default")
      (node (ref "M1_LED") (pin "A") (pinfunction "A_A") (pintype "passive"))
      (node (ref "U$49") (pin "P$2") (pinfunction "P$2_P$2") (pintype "bidirectional"))
    )
    (net (code "26") (name "Net-(M2_B-PadA)") (class "Default")
      (node (ref "M2_B") (pin "A") (pinfunction "A_A") (pintype "passive"))
      (node (ref "U$95") (pin "P$2") (pinfunction "P$2_P$2") (pintype "bidirectional"))
    )
    (net (code "27") (name "Net-(M2_F-PadK)") (class "Default")
      (node (ref "M2_F") (pin "K") (pinfunction "K_K") (pintype "passive"))
      (node (ref "U$96") (pin "P$2") (pinfunction "P$2_P$2") (pintype "bidirectional"))
    )
    (net (code "28") (name "Net-(M2_LED-PadA)") (class "Default")
      (node (ref "M2_LED") (pin "A") (pinfunction "A_A") (pintype "passive"))
      (node (ref "U$50") (pin "P$2") (pinfunction "P$2_P$2") (pintype "bidirectional"))
    )
    (net (code "29") (name "Net-(M3_B-PadA)") (class "Default")
      (node (ref "M3_B") (pin "A") (pinfunction "A_A") (pintype "passive"))
      (node (ref "U$97") (pin "P$2") (pinfunction "P$2_P$2") (pintype "bidirectional"))
    )
    (net (code "30") (name "Net-(M3_F-PadK)") (class "Default")
      (node (ref "M3_F") (pin "K") (pinfunction "K_K") (pintype "passive"))
      (node (ref "U$98") (pin "P$2") (pinfunction "P$2_P$2") (pintype "bidirectional"))
    )
    (net (code "31") (name "Net-(M3_LED-PadA)") (class "Default")
      (node (ref "M3_LED") (pin "A") (pinfunction "A_A") (pintype "passive"))
      (node (ref "U$51") (pin "P$2") (pinfunction "P$2_P$2") (pintype "bidirectional"))
    )
    (net (code "32") (name "Net-(M4_B-PadA)") (class "Default")
      (node (ref "M4_B") (pin "A") (pinfunction "A_A") (pintype "passive"))
      (node (ref "U$99") (pin "P$2") (pinfunction "P$2_P$2") (pintype "bidirectional"))
    )
    (net (code "33") (name "Net-(M4_F-PadK)") (class "Default")
      (node (ref "M4_F") (pin "K") (pinfunction "K_K") (pintype "passive"))
      (node (ref "U$104") (pin "P$2") (pinfunction "P$2_P$2") (pintype "bidirectional"))
    )
    (net (code "34") (name "Net-(M4_LED-PadA)") (class "Default")
      (node (ref "M4_LED") (pin "A") (pinfunction "A_A") (pintype "passive"))
      (node (ref "U$56") (pin "P$2") (pinfunction "P$2_P$2") (pintype "bidirectional"))
    )
    (net (code "35") (name "Net-(U$1-PadG)") (class "Default")
      (node (ref "U$1") (pin "G") (pinfunction "G_G") (pintype "bidirectional"))
      (node (ref "U$54") (pin "P$2") (pinfunction "P$2_P$2") (pintype "bidirectional"))
      (node (ref "U$55") (pin "P$2") (pinfunction "P$2_P$2") (pintype "bidirectional"))
    )
    (net (code "36") (name "Net-(U$2-PadG)") (class "Default")
      (node (ref "U$2") (pin "G") (pinfunction "G_G") (pintype "bidirectional"))
      (node (ref "U$62") (pin "P$2") (pinfunction "P$2_P$2") (pintype "bidirectional"))
      (node (ref "U$63") (pin "P$1") (pinfunction "P$1_P$1") (pintype "bidirectional"))
    )
    (net (code "37") (name "Net-(U$3-PadG)") (class "Default")
      (node (ref "U$3") (pin "G") (pinfunction "G_G") (pintype "bidirectional"))
      (node (ref "U$70") (pin "P$2") (pinfunction "P$2_P$2") (pintype "bidirectional"))
      (node (ref "U$71") (pin "P$2") (pinfunction "P$2_P$2") (pintype "bidirectional"))
    )
    (net (code "38") (name "Net-(U$4-PadG)") (class "Default")
      (node (ref "U$4") (pin "G") (pinfunction "G_G") (pintype "bidirectional"))
      (node (ref "U$72") (pin "P$2") (pinfunction "P$2_P$2") (pintype "bidirectional"))
      (node (ref "U$73") (pin "P$1") (pinfunction "P$1_P$1") (pintype "bidirectional"))
    )
    (net (code "39") (name "Net-(U$5-PadHO)") (class "Default")
      (node (ref "U$5") (pin "HO") (pinfunction "HO_HO") (pintype "bidirectional"))
      (node (ref "U$9") (pin "P$1") (pinfunction "P$1_P$1") (pintype "bidirectional"))
    )
    (net (code "40") (name "Net-(U$8-1)") (class "Default")
      (node (ref "U$5") (pin "VB") (pinfunction "VB_VB") (pintype "bidirectional"))
      (node (ref "U$6") (pin "P$2") (pinfunction "P$2_P$2") (pintype "bidirectional"))
      (node (ref "U$8") (pin "P$1") (pinfunction "1_P$1") (pintype "bidirectional"))
    )
    (net (code "41") (name "Net-(U$8-2)") (class "Default")
      (node (ref "M2") (pin "1") (pinfunction "1_1") (pintype "passive"))
      (node (ref "M2_B") (pin "K") (pinfunction "K_K") (pintype "passive"))
      (node (ref "M2_F") (pin "A") (pinfunction "A_A") (pintype "passive"))
      (node (ref "U$10") (pin "P$1") (pinfunction "P$1_P$1") (pintype "bidirectional"))
      (node (ref "U$21") (pin "S") (pinfunction "S_S") (pintype "bidirectional"))
      (node (ref "U$22") (pin "D") (pinfunction "D_D") (pintype "bidirectional"))
      (node (ref "U$22") (pin "DD") (pinfunction "D_DD") (pintype "bidirectional"))
      (node (ref "U$22") (pin "DDD") (pinfunction "D_DDD") (pintype "bidirectional"))
      (node (ref "U$22") (pin "DDDD") (pinfunction "D_DDDD") (pintype "bidirectional"))
      (node (ref "U$5") (pin "VS") (pinfunction "VS_VS") (pintype "bidirectional"))
      (node (ref "U$8") (pin "P$2") (pinfunction "2_P$2") (pintype "bidirectional"))
    )
    (net (code "42") (name "Net-(U$10-PadP$2)") (class "Default")
      (node (ref "U$10") (pin "P$2") (pinfunction "P$2_P$2") (pintype "bidirectional"))
      (node (ref "U$21") (pin "G") (pinfunction "G_G") (pintype "bidirectional"))
      (node (ref "U$9") (pin "P$2") (pinfunction "P$2_P$2") (pintype "bidirectional"))
    )
    (net (code "43") (name "Net-(U$11-PadP$2)") (class "Default")
      (node (ref "U$11") (pin "P$2") (pinfunction "P$2_P$2") (pintype "bidirectional"))
      (node (ref "U$12") (pin "P$1") (pinfunction "P$1_P$1") (pintype "bidirectional"))
      (node (ref "U$22") (pin "G") (pinfunction "G_G") (pintype "bidirectional"))
    )
    (net (code "44") (name "Net-(U$12-PadP$2)") (class "Default")
      (node (ref "U$12") (pin "P$2") (pinfunction "P$2_P$2") (pintype "bidirectional"))
      (node (ref "U$5") (pin "LO") (pinfunction "LO_LO") (pintype "bidirectional"))
    )
    (net (code "45") (name "Net-(U$13-PadHO)") (class "Default")
      (node (ref "U$13") (pin "HO") (pinfunction "HO_HO") (pintype "bidirectional"))
      (node (ref "U$17") (pin "P$1") (pinfunction "P$1_P$1") (pintype "bidirectional"))
    )
    (net (code "46") (name "Net-(U$13-PadLO)") (class "Default")
      (node (ref "U$13") (pin "LO") (pinfunction "LO_LO") (pintype "bidirectional"))
      (node (ref "U$20") (pin "P$2") (pinfunction "P$2_P$2") (pintype "bidirectional"))
    )
    (net (code "47") (name "Net-(U$16-1)") (class "Default")
      (node (ref "U$13") (pin "VB") (pinfunction "VB_VB") (pintype "bidirectional"))
      (node (ref "U$14") (pin "P$2") (pinfunction "P$2_P$2") (pintype "bidirectional"))
      (node (ref "U$16") (pin "P$1") (pinfunction "1_P$1") (pintype "bidirectional"))
    )
    (net (code "48") (name "Net-(U$16-2)") (class "Default")
      (node (ref "M2") (pin "2") (pinfunction "2_2") (pintype "passive"))
      (node (ref "U$13") (pin "VS") (pinfunction "VS_VS") (pintype "bidirectional"))
      (node (ref "U$16") (pin "P$2") (pinfunction "2_P$2") (pintype "bidirectional"))
      (node (ref "U$18") (pin "P$1") (pinfunction "P$1_P$1") (pintype "bidirectional"))
      (node (ref "U$23") (pin "S") (pinfunction "S_S") (pintype "bidirectional"))
      (node (ref "U$24") (pin "D") (pinfunction "D_D") (pintype "bidirectional"))
      (node (ref "U$24") (pin "DD") (pinfunction "D_DD") (pintype "bidirectional"))
      (node (ref "U$24") (pin "DDD") (pinfunction "D_DDD") (pintype "bidirectional"))
      (node (ref "U$24") (pin "DDDD") (pinfunction "D_DDDD") (pintype "bidirectional"))
      (node (ref "U$95") (pin "P$1") (pinfunction "P$1_P$1") (pintype "bidirectional"))
      (node (ref "U$96") (pin "P$1") (pinfunction "P$1_P$1") (pintype "bidirectional"))
    )
    (net (code "49") (name "Net-(U$17-PadP$2)") (class "Default")
      (node (ref "U$17") (pin "P$2") (pinfunction "P$2_P$2") (pintype "bidirectional"))
      (node (ref "U$18") (pin "P$2") (pinfunction "P$2_P$2") (pintype "bidirectional"))
      (node (ref "U$23") (pin "G") (pinfunction "G_G") (pintype "bidirectional"))
    )
    (net (code "50") (name "Net-(U$19-PadP$2)") (class "Default")
      (node (ref "U$19") (pin "P$2") (pinfunction "P$2_P$2") (pintype "bidirectional"))
      (node (ref "U$20") (pin "P$1") (pinfunction "P$1_P$1") (pintype "bidirectional"))
      (node (ref "U$24") (pin "G") (pinfunction "G_G") (pintype "bidirectional"))
    )
    (net (code "51") (name "Net-(U$25-PadHO)") (class "Default")
      (node (ref "U$25") (pin "HO") (pinfunction "HO_HO") (pintype "bidirectional"))
      (node (ref "U$29") (pin "P$1") (pinfunction "P$1_P$1") (pintype "bidirectional"))
    )
    (net (code "52") (name "Net-(U$25-PadLO)") (class "Default")
      (node (ref "U$25") (pin "LO") (pinfunction "LO_LO") (pintype "bidirectional"))
      (node (ref "U$32") (pin "P$2") (pinfunction "P$2_P$2") (pintype "bidirectional"))
    )
    (net (code "53") (name "Net-(U$28-1)") (class "Default")
      (node (ref "U$25") (pin "VB") (pinfunction "VB_VB") (pintype "bidirectional"))
      (node (ref "U$26") (pin "P$2") (pinfunction "P$2_P$2") (pintype "bidirectional"))
      (node (ref "U$28") (pin "P$1") (pinfunction "1_P$1") (pintype "bidirectional"))
    )
    (net (code "54") (name "Net-(U$28-2)") (class "Default")
      (node (ref "M3") (pin "1") (pinfunction "1_1") (pintype "passive"))
      (node (ref "M3_B") (pin "K") (pinfunction "K_K") (pintype "passive"))
      (node (ref "M3_F") (pin "A") (pinfunction "A_A") (pintype "passive"))
      (node (ref "U$25") (pin "VS") (pinfunction "VS_VS") (pintype "bidirectional"))
      (node (ref "U$28") (pin "P$2") (pinfunction "2_P$2") (pintype "bidirectional"))
      (node (ref "U$30") (pin "P$1") (pinfunction "P$1_P$1") (pintype "bidirectional"))
      (node (ref "U$41") (pin "S") (pinfunction "S_S") (pintype "bidirectional"))
      (node (ref "U$42") (pin "D") (pinfunction "D_D") (pintype "bidirectional"))
      (node (ref "U$42") (pin "DD") (pinfunction "D_DD") (pintype "bidirectional"))
      (node (ref "U$42") (pin "DDD") (pinfunction "D_DDD") (pintype "bidirectional"))
      (node (ref "U$42") (pin "DDDD") (pinfunction "D_DDDD") (pintype "bidirectional"))
    )
    (net (code "55") (name "Net-(U$29-PadP$2)") (class "Default")
      (node (ref "U$29") (pin "P$2") (pinfunction "P$2_P$2") (pintype "bidirectional"))
      (node (ref "U$30") (pin "P$2") (pinfunction "P$2_P$2") (pintype "bidirectional"))
      (node (ref "U$41") (pin "G") (pinfunction "G_G") (pintype "bidirectional"))
    )
    (net (code "56") (name "Net-(U$31-PadP$2)") (class "Default")
      (node (ref "U$31") (pin "P$2") (pinfunction "P$2_P$2") (pintype "bidirectional"))
      (node (ref "U$32") (pin "P$1") (pinfunction "P$1_P$1") (pintype "bidirectional"))
      (node (ref "U$42") (pin "G") (pinfunction "G_G") (pintype "bidirectional"))
    )
    (net (code "57") (name "Net-(U$33-PadHO)") (class "Default")
      (node (ref "U$33") (pin "HO") (pinfunction "HO_HO") (pintype "bidirectional"))
      (node (ref "U$37") (pin "P$1") (pinfunction "P$1_P$1") (pintype "bidirectional"))
    )
    (net (code "58") (name "Net-(U$33-PadLO)") (class "Default")
      (node (ref "U$33") (pin "LO") (pinfunction "LO_LO") (pintype "bidirectional"))
      (node (ref "U$40") (pin "P$2") (pinfunction "P$2_P$2") (pintype "bidirectional"))
    )
    (net (code "59") (name "Net-(U$36-1)") (class "Default")
      (node (ref "U$33") (pin "VB") (pinfunction "VB_VB") (pintype "bidirectional"))
      (node (ref "U$34") (pin "P$2") (pinfunction "P$2_P$2") (pintype "bidirectional"))
      (node (ref "U$36") (pin "P$1") (pinfunction "1_P$1") (pintype "bidirectional"))
    )
    (net (code "60") (name "Net-(U$36-2)") (class "Default")
      (node (ref "M3") (pin "2") (pinfunction "2_2") (pintype "passive"))
      (node (ref "U$33") (pin "VS") (pinfunction "VS_VS") (pintype "bidirectional"))
      (node (ref "U$36") (pin "P$2") (pinfunction "2_P$2") (pintype "bidirectional"))
      (node (ref "U$38") (pin "P$1") (pinfunction "P$1_P$1") (pintype "bidirectional"))
      (node (ref "U$43") (pin "S") (pinfunction "S_S") (pintype "bidirectional"))
      (node (ref "U$44") (pin "D") (pinfunction "D_D") (pintype "bidirectional"))
      (node (ref "U$44") (pin "DD") (pinfunction "D_DD") (pintype "bidirectional"))
      (node (ref "U$44") (pin "DDD") (pinfunction "D_DDD") (pintype "bidirectional"))
      (node (ref "U$44") (pin "DDDD") (pinfunction "D_DDDD") (pintype "bidirectional"))
      (node (ref "U$97") (pin "P$1") (pinfunction "P$1_P$1") (pintype "bidirectional"))
      (node (ref "U$98") (pin "P$1") (pinfunction "P$1_P$1") (pintype "bidirectional"))
    )
    (net (code "61") (name "Net-(U$37-PadP$2)") (class "Default")
      (node (ref "U$37") (pin "P$2") (pinfunction "P$2_P$2") (pintype "bidirectional"))
      (node (ref "U$38") (pin "P$2") (pinfunction "P$2_P$2") (pintype "bidirectional"))
      (node (ref "U$43") (pin "G") (pinfunction "G_G") (pintype "bidirectional"))
    )
    (net (code "62") (name "Net-(U$39-PadP$2)") (class "Default")
      (node (ref "U$39") (pin "P$2") (pinfunction "P$2_P$2") (pintype "bidirectional"))
      (node (ref "U$40") (pin "P$1") (pinfunction "P$1_P$1") (pintype "bidirectional"))
      (node (ref "U$44") (pin "G") (pinfunction "G_G") (pintype "bidirectional"))
    )
    (net (code "63") (name "Net-(U$45-PadHO)") (class "Default")
      (node (ref "U$45") (pin "HO") (pinfunction "HO_HO") (pintype "bidirectional"))
      (node (ref "U$54") (pin "P$1") (pinfunction "P$1_P$1") (pintype "bidirectional"))
    )
    (net (code "64") (name "Net-(U$45-PadLO)") (class "Default")
      (node (ref "U$45") (pin "LO") (pinfunction "LO_LO") (pintype "bidirectional"))
      (node (ref "U$63") (pin "P$2") (pinfunction "P$2_P$2") (pintype "bidirectional"))
    )
    (net (code "65") (name "Net-(U$48-1)") (class "Default")
      (node (ref "U$45") (pin "VB") (pinfunction "VB_VB") (pintype "bidirectional"))
      (node (ref "U$46") (pin "P$2") (pinfunction "P$2_P$2") (pintype "bidirectional"))
      (node (ref "U$48") (pin "P$1") (pinfunction "1_P$1") (pintype "bidirectional"))
    )
    (net (code "66") (name "Net-(U$48-2)") (class "Default")
      (node (ref "M1") (pin "1") (pinfunction "1_1") (pintype "passive"))
      (node (ref "M1_B") (pin "K") (pinfunction "K_K") (pintype "passive"))
      (node (ref "M1_F") (pin "A") (pinfunction "A_A") (pintype "passive"))
      (node (ref "U$1") (pin "S") (pinfunction "S_S") (pintype "bidirectional"))
      (node (ref "U$2") (pin "D") (pinfunction "D_D") (pintype "bidirectional"))
      (node (ref "U$2") (pin "DD") (pinfunction "D_DD") (pintype "bidirectional"))
      (node (ref "U$2") (pin "DDD") (pinfunction "D_DDD") (pintype "bidirectional"))
      (node (ref "U$2") (pin "DDDD") (pinfunction "D_DDDD") (pintype "bidirectional"))
      (node (ref "U$45") (pin "VS") (pinfunction "VS_VS") (pintype "bidirectional"))
      (node (ref "U$48") (pin "P$2") (pinfunction "2_P$2") (pintype "bidirectional"))
      (node (ref "U$55") (pin "P$1") (pinfunction "P$1_P$1") (pintype "bidirectional"))
    )
    (net (code "67") (name "Net-(U$53-P$2)") (class "Default")
      (node (ref "+12V") (pin "K") (pinfunction "K_K") (pintype "passive"))
      (node (ref "+3.3V") (pin "K") (pinfunction "K_K") (pintype "passive"))
      (node (ref "LED_1") (pin "K") (pinfunction "K_K") (pintype "passive"))
      (node (ref "LED_2") (pin "K") (pinfunction "K_K") (pintype "passive"))
      (node (ref "LED_3") (pin "K") (pinfunction "K_K") (pintype "passive"))
      (node (ref "LED_4") (pin "K") (pinfunction "K_K") (pintype "passive"))
      (node (ref "M1_LED") (pin "K") (pinfunction "K_K") (pintype "passive"))
      (node (ref "M2_LED") (pin "K") (pinfunction "K_K") (pintype "passive"))
      (node (ref "M3_LED") (pin "K") (pinfunction "K_K") (pintype "passive"))
      (node (ref "M4_LED") (pin "K") (pinfunction "K_K") (pintype "passive"))
      (node (ref "U$53") (pin "P$3") (pinfunction "P$2_P$3") (pintype "bidirectional"))
    )
    (net (code "68") (name "Net-(U$57-PadP$1)") (class "Default")
      (node (ref "U$57") (pin "P$1") (pinfunction "P$1_P$1") (pintype "bidirectional"))
      (node (ref "U$92") (pin "P$1") (pinfunction "P$1_P$1") (pintype "bidirectional"))
    )
    (net (code "69") (name "Net-(U$64-PadHO)") (class "Default")
      (node (ref "U$64") (pin "HO") (pinfunction "HO_HO") (pintype "bidirectional"))
      (node (ref "U$76") (pin "P$1") (pinfunction "P$1_P$1") (pintype "bidirectional"))
    )
    (net (code "70") (name "Net-(U$64-PadLO)") (class "Default")
      (node (ref "U$64") (pin "LO") (pinfunction "LO_LO") (pintype "bidirectional"))
      (node (ref "U$79") (pin "P$2") (pinfunction "P$2_P$2") (pintype "bidirectional"))
    )
    (net (code "71") (name "Net-(U$66-PadHO)") (class "Default")
      (node (ref "U$66") (pin "HO") (pinfunction "HO_HO") (pintype "bidirectional"))
      (node (ref "U$70") (pin "P$1") (pinfunction "P$1_P$1") (pintype "bidirectional"))
    )
    (net (code "72") (name "Net-(U$66-PadLO)") (class "Default")
      (node (ref "U$66") (pin "LO") (pinfunction "LO_LO") (pintype "bidirectional"))
      (node (ref "U$73") (pin "P$2") (pinfunction "P$2_P$2") (pintype "bidirectional"))
    )
    (net (code "73") (name "Net-(U$69-1)") (class "Default")
      (node (ref "U$66") (pin "VB") (pinfunction "VB_VB") (pintype "bidirectional"))
      (node (ref "U$67") (pin "P$2") (pinfunction "P$2_P$2") (pintype "bidirectional"))
      (node (ref "U$69") (pin "P$1") (pinfunction "1_P$1") (pintype "bidirectional"))
    )
    (net (code "74") (name "Net-(U$69-2)") (class "Default")
      (node (ref "M1") (pin "2") (pinfunction "2_2") (pintype "passive"))
      (node (ref "U$3") (pin "S") (pinfunction "S_S") (pintype "bidirectional"))
      (node (ref "U$4") (pin "D") (pinfunction "D_D") (pintype "bidirectional"))
      (node (ref "U$4") (pin "DD") (pinfunction "D_DD") (pintype "bidirectional"))
      (node (ref "U$4") (pin "DDD") (pinfunction "D_DDD") (pintype "bidirectional"))
      (node (ref "U$4") (pin "DDDD") (pinfunction "D_DDDD") (pintype "bidirectional"))
      (node (ref "U$66") (pin "VS") (pinfunction "VS_VS") (pintype "bidirectional"))
      (node (ref "U$69") (pin "P$2") (pinfunction "2_P$2") (pintype "bidirectional"))
      (node (ref "U$71") (pin "P$1") (pinfunction "P$1_P$1") (pintype "bidirectional"))
      (node (ref "U$93") (pin "P$1") (pinfunction "P$1_P$1") (pintype "bidirectional"))
      (node (ref "U$94") (pin "P$1") (pinfunction "P$1_P$1") (pintype "bidirectional"))
    )
    (net (code "75") (name "Net-(U$75-1)") (class "Default")
      (node (ref "U$64") (pin "VB") (pinfunction "VB_VB") (pintype "bidirectional"))
      (node (ref "U$65") (pin "P$2") (pinfunction "P$2_P$2") (pintype "bidirectional"))
      (node (ref "U$75") (pin "P$1") (pinfunction "1_P$1") (pintype "bidirectional"))
    )
    (net (code "76") (name "Net-(U$75-2)") (class "Default")
      (node (ref "M4") (pin "1") (pinfunction "1_1") (pintype "passive"))
      (node (ref "M4_B") (pin "K") (pinfunction "K_K") (pintype "passive"))
      (node (ref "M4_F") (pin "A") (pinfunction "A_A") (pintype "passive"))
      (node (ref "U$64") (pin "VS") (pinfunction "VS_VS") (pintype "bidirectional"))
      (node (ref "U$75") (pin "P$2") (pinfunction "2_P$2") (pintype "bidirectional"))
      (node (ref "U$77") (pin "P$1") (pinfunction "P$1_P$1") (pintype "bidirectional"))
      (node (ref "U$88") (pin "S") (pinfunction "S_S") (pintype "bidirectional"))
      (node (ref "U$89") (pin "D") (pinfunction "D_D") (pintype "bidirectional"))
      (node (ref "U$89") (pin "DD") (pinfunction "D_DD") (pintype "bidirectional"))
      (node (ref "U$89") (pin "DDD") (pinfunction "D_DDD") (pintype "bidirectional"))
      (node (ref "U$89") (pin "DDDD") (pinfunction "D_DDDD") (pintype "bidirectional"))
    )
    (net (code "77") (name "Net-(U$76-PadP$2)") (class "Default")
      (node (ref "U$76") (pin "P$2") (pinfunction "P$2_P$2") (pintype "bidirectional"))
      (node (ref "U$77") (pin "P$2") (pinfunction "P$2_P$2") (pintype "bidirectional"))
      (node (ref "U$88") (pin "G") (pinfunction "G_G") (pintype "bidirectional"))
    )
    (net (code "78") (name "Net-(U$78-PadP$2)") (class "Default")
      (node (ref "U$78") (pin "P$2") (pinfunction "P$2_P$2") (pintype "bidirectional"))
      (node (ref "U$79") (pin "P$1") (pinfunction "P$1_P$1") (pintype "bidirectional"))
      (node (ref "U$89") (pin "G") (pinfunction "G_G") (pintype "bidirectional"))
    )
    (net (code "79") (name "Net-(U$80-PadHO)") (class "Default")
      (node (ref "U$80") (pin "HO") (pinfunction "HO_HO") (pintype "bidirectional"))
      (node (ref "U$84") (pin "P$1") (pinfunction "P$1_P$1") (pintype "bidirectional"))
    )
    (net (code "80") (name "Net-(U$80-PadLO)") (class "Default")
      (node (ref "U$80") (pin "LO") (pinfunction "LO_LO") (pintype "bidirectional"))
      (node (ref "U$87") (pin "P$2") (pinfunction "P$2_P$2") (pintype "bidirectional"))
    )
    (net (code "81") (name "Net-(U$83-1)") (class "Default")
      (node (ref "U$80") (pin "VB") (pinfunction "VB_VB") (pintype "bidirectional"))
      (node (ref "U$81") (pin "P$2") (pinfunction "P$2_P$2") (pintype "bidirectional"))
      (node (ref "U$83") (pin "P$1") (pinfunction "1_P$1") (pintype "bidirectional"))
    )
    (net (code "82") (name "Net-(U$83-2)") (class "Default")
      (node (ref "M4") (pin "2") (pinfunction "2_2") (pintype "passive"))
      (node (ref "U$104") (pin "P$1") (pinfunction "P$1_P$1") (pintype "bidirectional"))
      (node (ref "U$80") (pin "VS") (pinfunction "VS_VS") (pintype "bidirectional"))
      (node (ref "U$83") (pin "P$2") (pinfunction "2_P$2") (pintype "bidirectional"))
      (node (ref "U$85") (pin "P$1") (pinfunction "P$1_P$1") (pintype "bidirectional"))
      (node (ref "U$90") (pin "S") (pinfunction "S_S") (pintype "bidirectional"))
      (node (ref "U$91") (pin "D") (pinfunction "D_D") (pintype "bidirectional"))
      (node (ref "U$91") (pin "DD") (pinfunction "D_DD") (pintype "bidirectional"))
      (node (ref "U$91") (pin "DDD") (pinfunction "D_DDD") (pintype "bidirectional"))
      (node (ref "U$91") (pin "DDDD") (pinfunction "D_DDDD") (pintype "bidirectional"))
      (node (ref "U$99") (pin "P$1") (pinfunction "P$1_P$1") (pintype "bidirectional"))
    )
    (net (code "83") (name "Net-(U$84-PadP$2)") (class "Default")
      (node (ref "U$84") (pin "P$2") (pinfunction "P$2_P$2") (pintype "bidirectional"))
      (node (ref "U$85") (pin "P$2") (pinfunction "P$2_P$2") (pintype "bidirectional"))
      (node (ref "U$90") (pin "G") (pinfunction "G_G") (pintype "bidirectional"))
    )
    (net (code "84") (name "Net-(U$86-PadP$2)") (class "Default")
      (node (ref "U$86") (pin "P$2") (pinfunction "P$2_P$2") (pintype "bidirectional"))
      (node (ref "U$87") (pin "P$1") (pinfunction "P$1_P$1") (pintype "bidirectional"))
      (node (ref "U$91") (pin "G") (pinfunction "G_G") (pintype "bidirectional"))
    )
    (net (code "85") (name "Net-(U$113-1)") (class "Default")
      (node (ref "U$112") (pin "P$1") (pinfunction "P$1_P$1") (pintype "bidirectional"))
      (node (ref "U$113") (pin "P$1") (pinfunction "1_P$1") (pintype "bidirectional"))
      (node (ref "U2") (pin "2") (pinfunction "PF0/OSC_IN_2") (pintype "bidirectional"))
    )
    (net (code "86") (name "Net-(U$114-1)") (class "Default")
      (node (ref "U$112") (pin "P$2") (pinfunction "P$2_P$2") (pintype "bidirectional"))
      (node (ref "U$114") (pin "P$1") (pinfunction "1_P$1") (pintype "bidirectional"))
      (node (ref "U2") (pin "3") (pinfunction "PF1/OSC_OUT_3") (pintype "bidirectional"))
    )
    (net (code "87") (name "Net-(U2-BOOT0)") (class "Default")
      (node (ref "U$107") (pin "P$2") (pinfunction "P$2_P$2") (pintype "bidirectional"))
      (node (ref "U2") (pin "31") (pinfunction "BOOT0_31") (pintype "input"))
    )
    (net (code "88") (name "PLED_1") (class "Default")
      (node (ref "U$49") (pin "P$1") (pinfunction "P$1_P$1") (pintype "bidirectional"))
      (node (ref "U2") (pin "18") (pinfunction "PA8_18") (pintype "bidirectional"))
    )
    (net (code "89") (name "PLED_2") (class "Default")
      (node (ref "U$50") (pin "P$1") (pinfunction "P$1_P$1") (pintype "bidirectional"))
      (node (ref "U2") (pin "21") (pinfunction "PA11_21") (pintype "bidirectional"))
    )
    (net (code "90") (name "PLED_3") (class "Default")
      (node (ref "U$51") (pin "P$1") (pinfunction "P$1_P$1") (pintype "bidirectional"))
      (node (ref "U2") (pin "22") (pinfunction "PA12_22") (pintype "bidirectional"))
    )
    (net (code "91") (name "PLED_4") (class "Default")
      (node (ref "U$56") (pin "P$1") (pinfunction "P$1_P$1") (pintype "bidirectional"))
      (node (ref "U2") (pin "28") (pinfunction "PB5_28") (pintype "bidirectional"))
    )
    (net (code "92") (name "RST") (class "Default")
      (node (ref "S2") (pin "1") (pinfunction "1_1") (pintype "bidirectional"))
      (node (ref "S2") (pin "2") (pinfunction "2_2") (pintype "bidirectional"))
      (node (ref "SV2") (pin "5") (pinfunction "5_5") (pintype "passive"))
      (node (ref "U$106") (pin "P$1") (pinfunction "P$1_P$1") (pintype "bidirectional"))
      (node (ref "U$111") (pin "P$1") (pinfunction "1_P$1") (pintype "bidirectional"))
      (node (ref "U2") (pin "4") (pinfunction "NRST_4") (pintype "bidirectional"))
      (node (ref "X1") (pin "5") (pinfunction "5_5") (pintype "passive"))
    )
    (net (code "93") (name "RX") (class "Default")
      (node (ref "TP10") (pin "TP") (pinfunction "TP_TP") (pintype "input"))
      (node (ref "U2") (pin "20") (pinfunction "PA10_20") (pintype "bidirectional"))
      (node (ref "X1") (pin "4") (pinfunction "4_4") (pintype "passive"))
    )
    (net (code "94") (name "SCL") (class "Default")
      (node (ref "TP11") (pin "TP") (pinfunction "TP_TP") (pintype "input"))
      (node (ref "U2") (pin "29") (pinfunction "PB6_29") (pintype "bidirectional"))
      (node (ref "X1") (pin "6") (pinfunction "6_6") (pintype "passive"))
    )
    (net (code "95") (name "SDA") (class "Default")
      (node (ref "TP12") (pin "TP") (pinfunction "TP_TP") (pintype "input"))
      (node (ref "U2") (pin "30") (pinfunction "PB7_30") (pintype "bidirectional"))
      (node (ref "X1") (pin "7") (pinfunction "7_7") (pintype "passive"))
    )
    (net (code "96") (name "SWO") (class "Default")
      (node (ref "SV2") (pin "6") (pinfunction "6_6") (pintype "passive"))
      (node (ref "U2") (pin "26") (pinfunction "PB3_26") (pintype "bidirectional"))
    )
    (net (code "97") (name "TCK") (class "Default")
      (node (ref "SV2") (pin "2") (pinfunction "2_2") (pintype "passive"))
      (node (ref "U2") (pin "24") (pinfunction "PA14_24") (pintype "bidirectional"))
    )
    (net (code "98") (name "TMS") (class "Default")
      (node (ref "SV2") (pin "4") (pinfunction "4_4") (pintype "passive"))
      (node (ref "U2") (pin "23") (pinfunction "PA13_23") (pintype "bidirectional"))
    )
    (net (code "99") (name "TX") (class "Default")
      (node (ref "TP9") (pin "TP") (pinfunction "TP_TP") (pintype "input"))
      (node (ref "U2") (pin "19") (pinfunction "PA9_19") (pintype "bidirectional"))
      (node (ref "X1") (pin "3") (pinfunction "3_3") (pintype "passive"))
    )
    (net (code "100") (name "VDD") (class "Default")
      (node (ref "U$1") (pin "D") (pinfunction "D_D") (pintype "bidirectional"))
      (node (ref "U$1") (pin "DD") (pinfunction "D_DD") (pintype "bidirectional"))
      (node (ref "U$1") (pin "DDD") (pinfunction "D_DDD") (pintype "bidirectional"))
      (node (ref "U$1") (pin "DDDD") (pinfunction "D_DDDD") (pintype "bidirectional"))
      (node (ref "U$101") (pin "P$1") (pinfunction "P$1_P$1") (pintype "bidirectional"))
      (node (ref "U$102") (pin "P$2") (pinfunction "P$2_P$2") (pintype "bidirectional"))
      (node (ref "U$13") (pin "VCC") (pinfunction "VCC_VCC") (pintype "bidirectional"))
      (node (ref "U$14") (pin "P$1") (pinfunction "P$1_P$1") (pintype "bidirectional"))
      (node (ref "U$15") (pin "P$1") (pinfunction "1_P$1") (pintype "bidirectional"))
      (node (ref "U$21") (pin "D") (pinfunction "D_D") (pintype "bidirectional"))
      (node (ref "U$21") (pin "DD") (pinfunction "D_DD") (pintype "bidirectional"))
      (node (ref "U$21") (pin "DDD") (pinfunction "D_DDD") (pintype "bidirectional"))
      (node (ref "U$21") (pin "DDDD") (pinfunction "D_DDDD") (pintype "bidirectional"))
      (node (ref "U$23") (pin "D") (pinfunction "D_D") (pintype "bidirectional"))
      (node (ref "U$23") (pin "DD") (pinfunction "D_DD") (pintype "bidirectional"))
      (node (ref "U$23") (pin "DDD") (pinfunction "D_DDD") (pintype "bidirectional"))
      (node (ref "U$23") (pin "DDDD") (pinfunction "D_DDDD") (pintype "bidirectional"))
      (node (ref "U$25") (pin "VCC") (pinfunction "VCC_VCC") (pintype "bidirectional"))
      (node (ref "U$26") (pin "P$1") (pinfunction "P$1_P$1") (pintype "bidirectional"))
      (node (ref "U$27") (pin "P$1") (pinfunction "1_P$1") (pintype "bidirectional"))
      (node (ref "U$3") (pin "D") (pinfunction "D_D") (pintype "bidirectional"))
      (node (ref "U$3") (pin "DD") (pinfunction "D_DD") (pintype "bidirectional"))
      (node (ref "U$3") (pin "DDD") (pinfunction "D_DDD") (pintype "bidirectional"))
      (node (ref "U$3") (pin "DDDD") (pinfunction "D_DDDD") (pintype "bidirectional"))
      (node (ref "U$33") (pin "VCC") (pinfunction "VCC_VCC") (pintype "bidirectional"))
      (node (ref "U$34") (pin "P$1") (pinfunction "P$1_P$1") (pintype "bidirectional"))
      (node (ref "U$35") (pin "P$1") (pinfunction "1_P$1") (pintype "bidirectional"))
      (node (ref "U$41") (pin "D") (pinfunction "D_D") (pintype "bidirectional"))
      (node (ref "U$41") (pin "DD") (pinfunction "D_DD") (pintype "bidirectional"))
      (node (ref "U$41") (pin "DDD") (pinfunction "D_DDD") (pintype "bidirectional"))
      (node (ref "U$41") (pin "DDDD") (pinfunction "D_DDDD") (pintype "bidirectional"))
      (node (ref "U$43") (pin "D") (pinfunction "D_D") (pintype "bidirectional"))
      (node (ref "U$43") (pin "DD") (pinfunction "D_DD") (pintype "bidirectional"))
      (node (ref "U$43") (pin "DDD") (pinfunction "D_DDD") (pintype "bidirectional"))
      (node (ref "U$43") (pin "DDDD") (pinfunction "D_DDDD") (pintype "bidirectional"))
      (node (ref "U$45") (pin "VCC") (pinfunction "VCC_VCC") (pintype "bidirectional"))
      (node (ref "U$46") (pin "P$1") (pinfunction "P$1_P$1") (pintype "bidirectional"))
      (node (ref "U$47") (pin "P$1") (pinfunction "1_P$1") (pintype "bidirectional"))
      (node (ref "U$5") (pin "VCC") (pinfunction "VCC_VCC") (pintype "bidirectional"))
      (node (ref "U$6") (pin "P$1") (pinfunction "P$1_P$1") (pintype "bidirectional"))
      (node (ref "U$64") (pin "VCC") (pinfunction "VCC_VCC") (pintype "bidirectional"))
      (node (ref "U$65") (pin "P$1") (pinfunction "P$1_P$1") (pintype "bidirectional"))
      (node (ref "U$66") (pin "VCC") (pinfunction "VCC_VCC") (pintype "bidirectional"))
      (node (ref "U$67") (pin "P$1") (pinfunction "P$1_P$1") (pintype "bidirectional"))
      (node (ref "U$68") (pin "P$1") (pinfunction "1_P$1") (pintype "bidirectional"))
      (node (ref "U$7") (pin "P$1") (pinfunction "1_P$1") (pintype "bidirectional"))
      (node (ref "U$74") (pin "P$1") (pinfunction "1_P$1") (pintype "bidirectional"))
      (node (ref "U$80") (pin "VCC") (pinfunction "VCC_VCC") (pintype "bidirectional"))
      (node (ref "U$81") (pin "P$1") (pinfunction "P$1_P$1") (pintype "bidirectional"))
      (node (ref "U$82") (pin "P$1") (pinfunction "1_P$1") (pintype "bidirectional"))
      (node (ref "U$88") (pin "D") (pinfunction "D_D") (pintype "bidirectional"))
      (node (ref "U$88") (pin "DD") (pinfunction "D_DD") (pintype "bidirectional"))
      (node (ref "U$88") (pin "DDD") (pinfunction "D_DDD") (pintype "bidirectional"))
      (node (ref "U$88") (pin "DDDD") (pinfunction "D_DDDD") (pintype "bidirectional"))
      (node (ref "U$90") (pin "D") (pinfunction "D_D") (pintype "bidirectional"))
      (node (ref "U$90") (pin "DD") (pinfunction "D_DD") (pintype "bidirectional"))
      (node (ref "U$90") (pin "DDD") (pinfunction "D_DDD") (pintype "bidirectional"))
      (node (ref "U$90") (pin "DDDD") (pinfunction "D_DDDD") (pintype "bidirectional"))
      (node (ref "U$92") (pin "P$2") (pinfunction "P$2_P$2") (pintype "bidirectional"))
    )
    (net (code "101") (name "unconnected-(U$5-PadSD)") (class "Default")
      (node (ref "U$5") (pin "SD") (pinfunction "SD_SD") (pintype "bidirectional"))
    )
    (net (code "102") (name "unconnected-(U$13-PadSD)") (class "Default")
      (node (ref "U$13") (pin "SD") (pinfunction "SD_SD") (pintype "bidirectional"))
    )
    (net (code "103") (name "unconnected-(U$25-PadSD)") (class "Default")
      (node (ref "U$25") (pin "SD") (pinfunction "SD_SD") (pintype "bidirectional"))
    )
    (net (code "104") (name "unconnected-(U$33-PadSD)") (class "Default")
      (node (ref "U$33") (pin "SD") (pinfunction "SD_SD") (pintype "bidirectional"))
    )
    (net (code "105") (name "unconnected-(U$45-PadSD)") (class "Default")
      (node (ref "U$45") (pin "SD") (pinfunction "SD_SD") (pintype "bidirectional"))
    )
    (net (code "106") (name "unconnected-(U$53-P$3-PadP$2)") (class "Default")
      (node (ref "U$53") (pin "P$2") (pinfunction "P$3_P$2") (pintype "bidirectional"))
    )
    (net (code "107") (name "unconnected-(U$64-PadSD)") (class "Default")
      (node (ref "U$64") (pin "SD") (pinfunction "SD_SD") (pintype "bidirectional"))
    )
    (net (code "108") (name "unconnected-(U$66-PadSD)") (class "Default")
      (node (ref "U$66") (pin "SD") (pinfunction "SD_SD") (pintype "bidirectional"))
    )
    (net (code "109") (name "unconnected-(U$80-PadSD)") (class "Default")
      (node (ref "U$80") (pin "SD") (pinfunction "SD_SD") (pintype "bidirectional"))
    )
  )
)
